# Indicators.net
KiCad netlist of a schematic drawn in Altium Designer
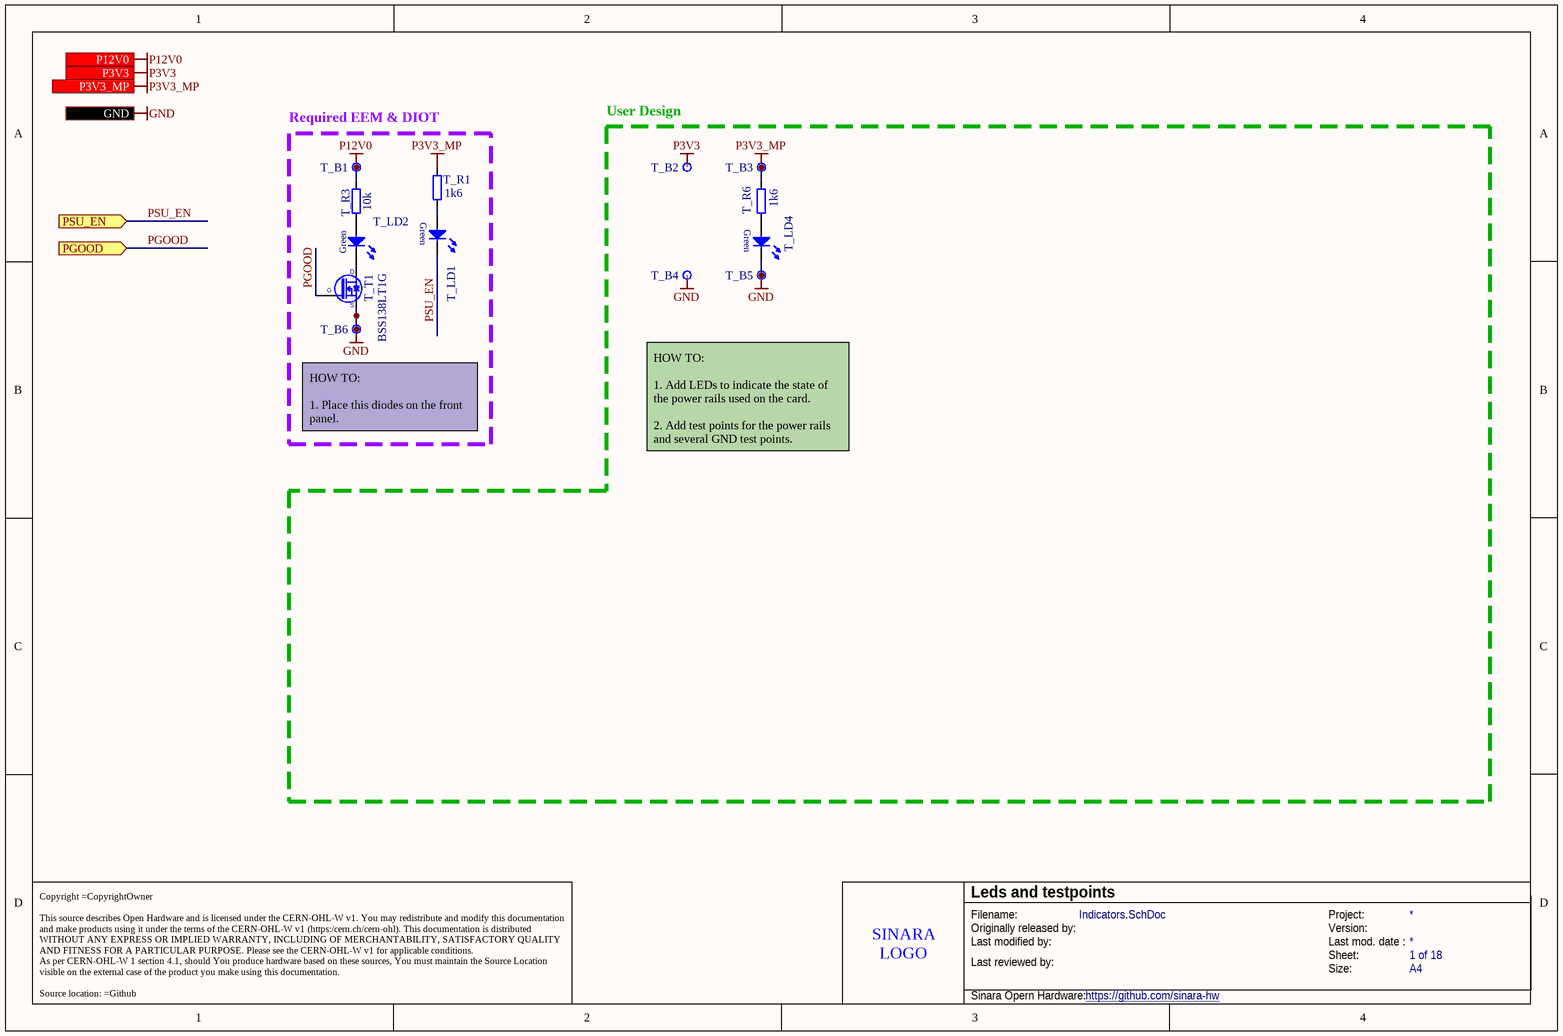
[diagram p0: Indicators.SchDoc]

(export (version "E")
  (design (tool "Eeschema 10.0.6"))
  (components
    (comp (ref "T_B1")
      (value "Plated Hole")
      (footprint "c150h50")
      (description "Single Terminal Socket")
      (fields (field (name "PART NUMBER") "PLATED_HOLE0.5_PAD1.5") (field (name "AUTHOR") "CERN DEM MR"))
      (libsource (lib "Eletro-mechanical") (part "Single Terminal Socket"))
    )
    (comp (ref "T_B2")
      (value "Plated Hole")
      (footprint "c150h50")
      (description "Single Terminal Socket")
      (fields (field (name "PART NUMBER") "PLATED_HOLE0.5_PAD1.5") (field (name "AUTHOR") "CERN DEM MR"))
      (libsource (lib "Eletro-mechanical") (part "Single Terminal Socket"))
    )
    (comp (ref "T_B3")
      (value "Plated Hole")
      (footprint "c150h50")
      (description "Single Terminal Socket")
      (fields (field (name "PART NUMBER") "PLATED_HOLE0.5_PAD1.5") (field (name "AUTHOR") "CERN DEM MR"))
      (libsource (lib "Eletro-mechanical") (part "Single Terminal Socket"))
    )
    (comp (ref "T_B4")
      (value "Plated Hole")
      (footprint "c150h50")
      (description "Single Terminal Socket")
      (fields (field (name "PART NUMBER") "PLATED_HOLE0.5_PAD1.5") (field (name "AUTHOR") "CERN DEM MR"))
      (libsource (lib "Eletro-mechanical") (part "Single Terminal Socket"))
    )
    (comp (ref "T_B5")
      (value "Plated Hole")
      (footprint "c150h50")
      (description "Single Terminal Socket")
      (fields (field (name "PART NUMBER") "PLATED_HOLE0.5_PAD1.5") (field (name "AUTHOR") "CERN DEM MR"))
      (libsource (lib "Eletro-mechanical") (part "Single Terminal Socket"))
    )
    (comp (ref "T_B6")
      (value "Plated Hole")
      (footprint "c150h50")
      (description "Single Terminal Socket")
      (fields (field (name "PART NUMBER") "PLATED_HOLE0.5_PAD1.5") (field (name "AUTHOR") "CERN DEM MR"))
      (libsource (lib "Eletro-mechanical") (part "Single Terminal Socket"))
    )
    (comp (ref "T_LD1")
      (value "Green")
      (footprint "LED_KINGBRIGHT_KPH-1608CGCKr")
      (description "Green 0603")
      (fields
        (field (name "PART NUMBER") "LED_KINGBRIGHT_KPH-1608CGCK")
        (field (name "MANUFACTURER") "KINGBRIGHT")
        (field (name "AUTHOR") "CERN DEM JLC")
      )
      (libsource (lib "LIBRARY_SCH") (part "LED_0603_Green"))
    )
    (comp (ref "T_LD2")
      (value "Green")
      (footprint "LED_AVAGO_HSME-C120")
      (description "LED Green 1C 2A")
      (fields
        (field (name "PART NUMBER") "LED_AVAGO_HSME-C120")
        (field (name "MANUFACTURER") "AVAGO TECHNOLOGIES")
        (field (name "AUTHOR") "CERN DEM JMW")
      )
      (libsource (lib "ICs And Semiconductors") (part "LED Green 1C 2A"))
    )
    (comp (ref "T_LD4")
      (value "Green")
      (footprint "LED_KINGBRIGHT_KPH-1608CGCK")
      (description "LED Green 1C 2A")
      (fields
        (field (name "PART NUMBER") "LED_KINGBRIGHT_KPH-1608CGCK")
        (field (name "MANUFACTURER") "KINGBRIGHT")
        (field (name "AUTHOR") "CERN DEM JLC")
      )
      (libsource (lib "") (part "LED Green 1C 2A_1"))
    )
    (comp (ref "T_R1")
      (value "1k6")
      (footprint "RESC1005X40N")
      (description "Resistor - 1%")
      (fields
        (field (name "PART NUMBER") "R0402_1K6_1%_0.0625W_100PPM")
        (field (name "POWER") "0.0625W")
        (field (name "AUTHOR") "CERN DEM JLC")
      )
      (libsource (lib "Resistors") (part "Resistor - 1%"))
    )
    (comp (ref "T_R3")
      (value "10k")
      (footprint "RESC1608X55N")
      (description "Resistor - 1%")
      (fields
        (field (name "PART NUMBER") "R0603_10K_1%_0.1W_100PPM")
        (field (name "POWER") "0.1W")
        (field (name "AUTHOR") "CERN DEM JLC")
      )
      (libsource (lib "Resistors") (part "Resistor - 1%"))
    )
    (comp (ref "T_R6")
      (value "1k6")
      (footprint "RESC1005X40N")
      (description "Resistor - 1%")
      (fields
        (field (name "PART NUMBER") "R0402_1K6_1%_0.0625W_100PPM")
        (field (name "POWER") "0.0625W")
        (field (name "AUTHOR") "CERN DEM JLC")
      )
      (libsource (lib "Resistors") (part "Resistor - 1%"))
    )
    (comp (ref "T_T1")
      (value "BSS138LT1G")
      (footprint "SOT95P240X110-3N")
      (description "N-CHANNEL MOSFET WITH DIODE")
      (fields
        (field (name "MANUFACTURER") "ON SEMICONDUCTOR")
        (field (name "MANUFACTURER PART NUMBER") "BSS138L")
        (field (name "AUTHOR") "CERN DEM JLC")
      )
      (libsource (lib "ICs And Semiconductors") (part "N-MOSFET-D 1G 2S 3D"))
    )
  )
  (nets
    (net (code "1") (name "/PGOOD") (class "Default")
      (node (ref "T_T1") (pin "1") (pinfunction "G_1") (pintype "passive"))
    )
    (net (code "2") (name "/PSU_EN") (class "Default")
      (node (ref "T_LD1") (pin "1") (pinfunction "C_1") (pintype "passive"))
    )
    (net (code "3") (name "GND") (class "Default")
      (node (ref "T_B4") (pin "1") (pinfunction "1_1") (pintype "bidirectional"))
      (node (ref "T_B5") (pin "1") (pinfunction "1_1") (pintype "bidirectional"))
      (node (ref "T_B6") (pin "1") (pinfunction "1_1") (pintype "bidirectional"))
      (node (ref "T_LD4") (pin "1") (pinfunction "C_1") (pintype "passive"))
      (node (ref "T_T1") (pin "2") (pinfunction "S_2") (pintype "passive"))
    )
    (net (code "4") (name "Net-(T_LD1-A)") (class "Default")
      (node (ref "T_LD1") (pin "2") (pinfunction "A_2") (pintype "passive"))
      (node (ref "T_R1") (pin "1") (pinfunction "1_1") (pintype "passive"))
    )
    (net (code "5") (name "Net-(T_LD2-A)") (class "Default")
      (node (ref "T_LD2") (pin "2") (pinfunction "A_2") (pintype "passive"))
      (node (ref "T_R3") (pin "2") (pinfunction "2_2") (pintype "passive"))
    )
    (net (code "6") (name "Net-(T_LD2-C)") (class "Default")
      (node (ref "T_LD2") (pin "1") (pinfunction "C_1") (pintype "passive"))
      (node (ref "T_T1") (pin "3") (pinfunction "D_3") (pintype "passive"))
    )
    (net (code "7") (name "Net-(T_LD4-A)") (class "Default")
      (node (ref "T_LD4") (pin "2") (pinfunction "A_2") (pintype "passive"))
      (node (ref "T_R6") (pin "1") (pinfunction "1_1") (pintype "passive"))
    )
    (net (code "8") (name "P3V3") (class "Default")
      (node (ref "T_B2") (pin "1") (pinfunction "1_1") (pintype "bidirectional"))
    )
    (net (code "9") (name "P3V3_MP") (class "Default")
      (node (ref "T_B3") (pin "1") (pinfunction "1_1") (pintype "bidirectional"))
      (node (ref "T_R1") (pin "2") (pinfunction "2_2") (pintype "passive"))
      (node (ref "T_R6") (pin "2") (pinfunction "2_2") (pintype "passive"))
    )
    (net (code "10") (name "P12V0") (class "Default")
      (node (ref "T_B1") (pin "1") (pinfunction "1_1") (pintype "bidirectional"))
      (node (ref "T_R3") (pin "1") (pinfunction "1_1") (pintype "passive"))
    )
  )
)
